# 3v3_Regulator.net
KiCad netlist of a schematic drawn in Altium Designer
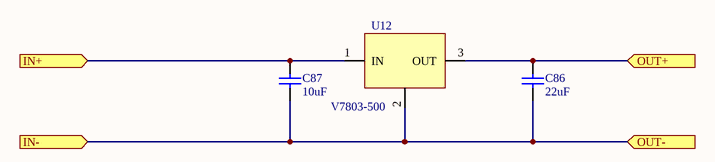
[diagram p0: 3v3_Regulator.SchDoc]

(export (version "E")
  (design (tool "Eeschema 10.0.6"))
  (components
    (comp (ref "C86")
      (value "22uF")
      (footprint "STD_0805_C")
      (description "Capacitor, 22uF, 0805, 25V")
      (libsource (lib "Arturo_Approved") (part "GRM21BR61E226ME44L"))
    )
    (comp (ref "C87")
      (value "10uF")
      (footprint "STD_0805_C")
      (description "Capacitor, 22uF, 0805, 25V")
      (libsource (lib "Arturo_Approved") (part "GRM21BR61E226ME44L"))
    )
    (comp (ref "U12")
      (value "V7803-500")
      (footprint "V78-500")
      (libsource (lib "Arturo_Approved") (part "V7803-500"))
    )
  )
  (nets
    (net (code "1") (name "/IN+") (class "Default")
      (node (ref "C87") (pin "2") (pinfunction "2_2") (pintype "passive"))
      (node (ref "U12") (pin "1") (pinfunction "IN_1") (pintype "passive"))
    )
    (net (code "2") (name "/IN-") (class "Default")
      (node (ref "C86") (pin "1") (pinfunction "1_1") (pintype "passive"))
      (node (ref "C87") (pin "1") (pinfunction "1_1") (pintype "passive"))
      (node (ref "U12") (pin "2") (pinfunction "GND_2") (pintype "passive"))
    )
    (net (code "3") (name "/OUT+") (class "Default")
      (node (ref "C86") (pin "2") (pinfunction "2_2") (pintype "passive"))
      (node (ref "U12") (pin "3") (pinfunction "OUT_3") (pintype "passive"))
    )
  )
)
